# fib_backplate.net
KiCad netlist of a schematic drawn in EAGLE
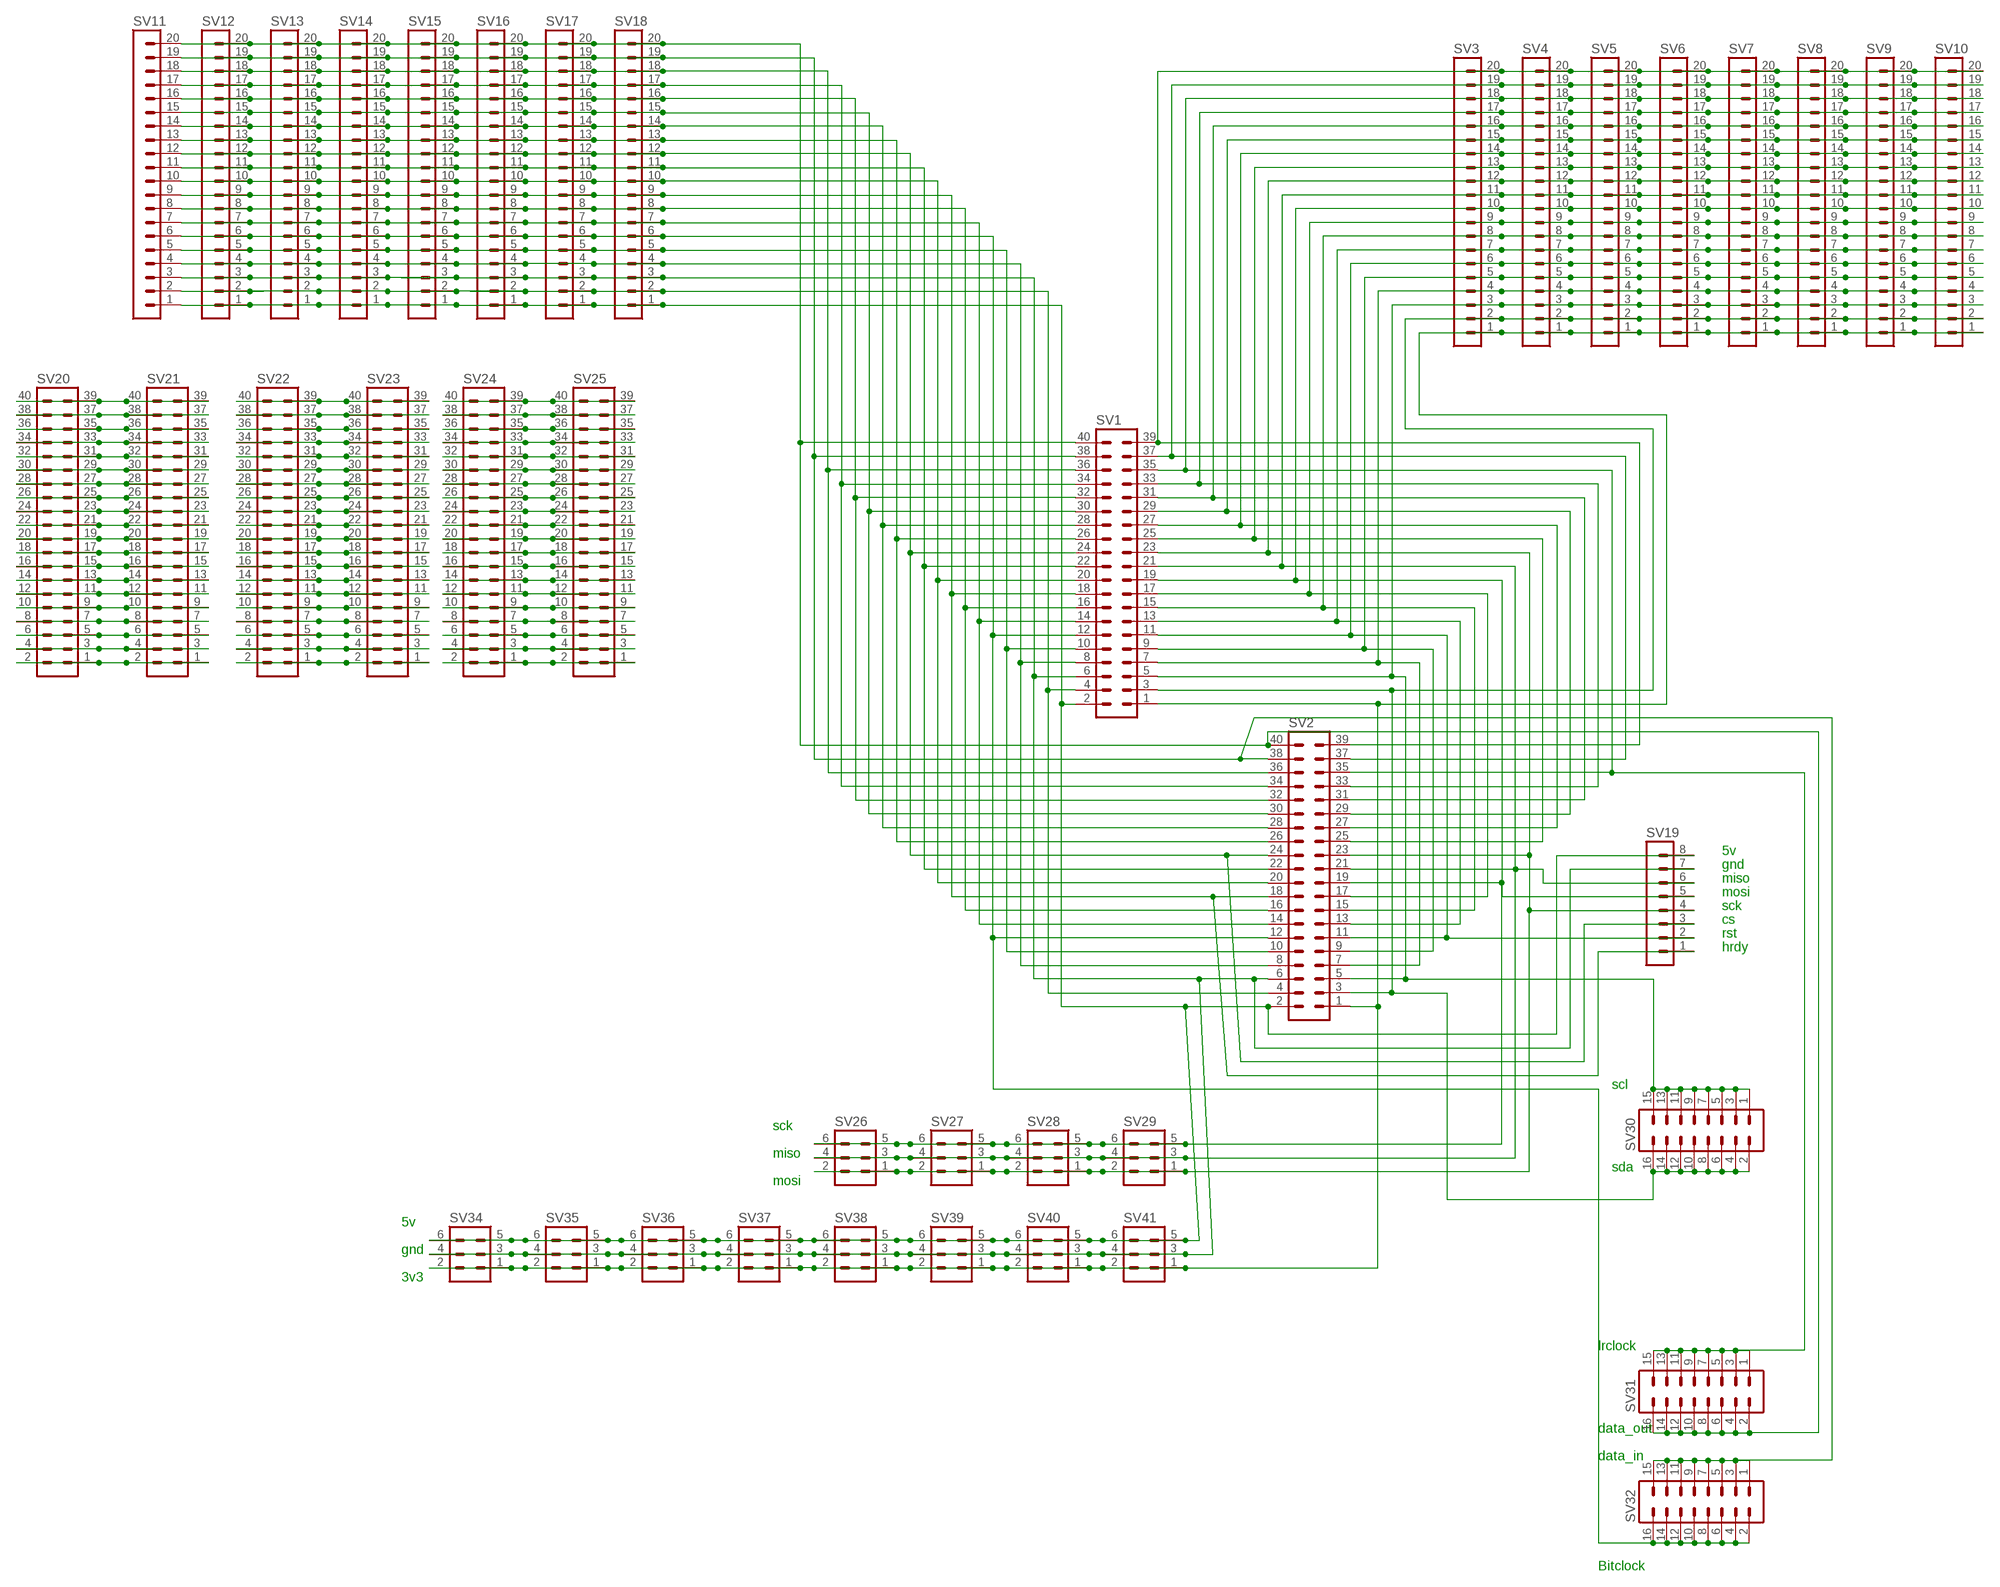
[diagram p0: schematic, sheet 1]

(export (version "E")
  (design (tool "Eeschema 10.0.6"))
  (components
    (comp (ref "SV1")
      (value "MA20-2")
      (footprint "eagle-import:MA20-2")
      (libsource (lib "eagle-import") (part "MA20-2"))
    )
    (comp (ref "SV2")
      (value "MA20-2")
      (footprint "eagle-import:MA20-2")
      (libsource (lib "eagle-import") (part "MA20-2"))
    )
    (comp (ref "SV3")
      (value "MA20-1L")
      (footprint "eagle-import:MA20-1L")
      (libsource (lib "eagle-import") (part "MA20-1L"))
    )
    (comp (ref "SV4")
      (value "MA20-1L")
      (footprint "eagle-import:MA20-1L")
      (libsource (lib "eagle-import") (part "MA20-1L"))
    )
    (comp (ref "SV5")
      (value "MA20-1L")
      (footprint "eagle-import:MA20-1L")
      (libsource (lib "eagle-import") (part "MA20-1L"))
    )
    (comp (ref "SV6")
      (value "MA20-1L")
      (footprint "eagle-import:MA20-1L")
      (libsource (lib "eagle-import") (part "MA20-1L"))
    )
    (comp (ref "SV7")
      (value "MA20-1L")
      (footprint "eagle-import:MA20-1L")
      (libsource (lib "eagle-import") (part "MA20-1L"))
    )
    (comp (ref "SV8")
      (value "MA20-1L")
      (footprint "eagle-import:MA20-1L")
      (libsource (lib "eagle-import") (part "MA20-1L"))
    )
    (comp (ref "SV9")
      (value "MA20-1L")
      (footprint "eagle-import:MA20-1L")
      (libsource (lib "eagle-import") (part "MA20-1L"))
    )
    (comp (ref "SV10")
      (value "MA20-1L")
      (footprint "eagle-import:MA20-1L")
      (libsource (lib "eagle-import") (part "MA20-1L"))
    )
    (comp (ref "SV11")
      (value "MA20-1L")
      (footprint "eagle-import:MA20-1L")
      (libsource (lib "eagle-import") (part "MA20-1L"))
    )
    (comp (ref "SV12")
      (value "MA20-1L")
      (footprint "eagle-import:MA20-1L")
      (libsource (lib "eagle-import") (part "MA20-1L"))
    )
    (comp (ref "SV13")
      (value "MA20-1L")
      (footprint "eagle-import:MA20-1L")
      (libsource (lib "eagle-import") (part "MA20-1L"))
    )
    (comp (ref "SV14")
      (value "MA20-1L")
      (footprint "eagle-import:MA20-1L")
      (libsource (lib "eagle-import") (part "MA20-1L"))
    )
    (comp (ref "SV15")
      (value "MA20-1L")
      (footprint "eagle-import:MA20-1L")
      (libsource (lib "eagle-import") (part "MA20-1L"))
    )
    (comp (ref "SV16")
      (value "MA20-1L")
      (footprint "eagle-import:MA20-1L")
      (libsource (lib "eagle-import") (part "MA20-1L"))
    )
    (comp (ref "SV17")
      (value "MA20-1L")
      (footprint "eagle-import:MA20-1L")
      (libsource (lib "eagle-import") (part "MA20-1L"))
    )
    (comp (ref "SV18")
      (value "MA20-1L")
      (footprint "eagle-import:MA20-1L")
      (libsource (lib "eagle-import") (part "MA20-1L"))
    )
    (comp (ref "SV19")
      (value "MA08-1")
      (footprint "eagle-import:MA08-1")
      (libsource (lib "eagle-import") (part "MA08-1"))
    )
    (comp (ref "SV20")
      (value "MA20-2")
      (footprint "eagle-import:MA20-2")
      (libsource (lib "eagle-import") (part "MA20-2"))
    )
    (comp (ref "SV21")
      (value "MA20-2")
      (footprint "eagle-import:MA20-2")
      (libsource (lib "eagle-import") (part "MA20-2"))
    )
    (comp (ref "SV22")
      (value "MA20-2")
      (footprint "eagle-import:MA20-2")
      (libsource (lib "eagle-import") (part "MA20-2"))
    )
    (comp (ref "SV23")
      (value "MA20-2")
      (footprint "eagle-import:MA20-2")
      (libsource (lib "eagle-import") (part "MA20-2"))
    )
    (comp (ref "SV24")
      (value "MA20-2")
      (footprint "eagle-import:MA20-2")
      (libsource (lib "eagle-import") (part "MA20-2"))
    )
    (comp (ref "SV25")
      (value "MA20-2")
      (footprint "eagle-import:MA20-2")
      (libsource (lib "eagle-import") (part "MA20-2"))
    )
    (comp (ref "SV26")
      (value "MA03-2")
      (footprint "eagle-import:MA03-2")
      (libsource (lib "eagle-import") (part "MA03-2"))
    )
    (comp (ref "SV27")
      (value "MA03-2")
      (footprint "eagle-import:MA03-2")
      (libsource (lib "eagle-import") (part "MA03-2"))
    )
    (comp (ref "SV28")
      (value "MA03-2")
      (footprint "eagle-import:MA03-2")
      (libsource (lib "eagle-import") (part "MA03-2"))
    )
    (comp (ref "SV29")
      (value "MA03-2")
      (footprint "eagle-import:MA03-2")
      (libsource (lib "eagle-import") (part "MA03-2"))
    )
    (comp (ref "SV30")
      (value "MA08-2")
      (footprint "eagle-import:MA08-2")
      (libsource (lib "eagle-import") (part "MA08-2"))
    )
    (comp (ref "SV31")
      (value "MA08-2")
      (footprint "eagle-import:MA08-2")
      (libsource (lib "eagle-import") (part "MA08-2"))
    )
    (comp (ref "SV32")
      (value "MA08-2")
      (footprint "eagle-import:MA08-2")
      (libsource (lib "eagle-import") (part "MA08-2"))
    )
    (comp (ref "SV34")
      (value "MA03-2")
      (footprint "eagle-import:MA03-2")
      (libsource (lib "eagle-import") (part "MA03-2"))
    )
    (comp (ref "SV35")
      (value "MA03-2")
      (footprint "eagle-import:MA03-2")
      (libsource (lib "eagle-import") (part "MA03-2"))
    )
    (comp (ref "SV36")
      (value "MA03-2")
      (footprint "eagle-import:MA03-2")
      (libsource (lib "eagle-import") (part "MA03-2"))
    )
    (comp (ref "SV37")
      (value "MA03-2")
      (footprint "eagle-import:MA03-2")
      (libsource (lib "eagle-import") (part "MA03-2"))
    )
    (comp (ref "SV38")
      (value "MA03-2")
      (footprint "eagle-import:MA03-2")
      (libsource (lib "eagle-import") (part "MA03-2"))
    )
    (comp (ref "SV39")
      (value "MA03-2")
      (footprint "eagle-import:MA03-2")
      (libsource (lib "eagle-import") (part "MA03-2"))
    )
    (comp (ref "SV40")
      (value "MA03-2")
      (footprint "eagle-import:MA03-2")
      (libsource (lib "eagle-import") (part "MA03-2"))
    )
    (comp (ref "SV41")
      (value "MA03-2")
      (footprint "eagle-import:MA03-2")
      (libsource (lib "eagle-import") (part "MA03-2"))
    )
  )
  (nets
    (net (code "1") (name "Net-(SV1-Pad1)") (class "Default")
      (node (ref "SV1") (pin "1") (pinfunction "1_1") (pintype "passive"))
      (node (ref "SV10") (pin "1") (pinfunction "1_1") (pintype "passive"))
      (node (ref "SV2") (pin "1") (pinfunction "1_1") (pintype "passive"))
      (node (ref "SV3") (pin "1") (pinfunction "1_1") (pintype "passive"))
      (node (ref "SV34") (pin "1") (pinfunction "1_1") (pintype "passive"))
      (node (ref "SV34") (pin "2") (pinfunction "2_2") (pintype "passive"))
      (node (ref "SV35") (pin "1") (pinfunction "1_1") (pintype "passive"))
      (node (ref "SV35") (pin "2") (pinfunction "2_2") (pintype "passive"))
      (node (ref "SV36") (pin "1") (pinfunction "1_1") (pintype "passive"))
      (node (ref "SV36") (pin "2") (pinfunction "2_2") (pintype "passive"))
      (node (ref "SV37") (pin "1") (pinfunction "1_1") (pintype "passive"))
      (node (ref "SV37") (pin "2") (pinfunction "2_2") (pintype "passive"))
      (node (ref "SV38") (pin "1") (pinfunction "1_1") (pintype "passive"))
      (node (ref "SV38") (pin "2") (pinfunction "2_2") (pintype "passive"))
      (node (ref "SV39") (pin "1") (pinfunction "1_1") (pintype "passive"))
      (node (ref "SV39") (pin "2") (pinfunction "2_2") (pintype "passive"))
      (node (ref "SV4") (pin "1") (pinfunction "1_1") (pintype "passive"))
      (node (ref "SV40") (pin "1") (pinfunction "1_1") (pintype "passive"))
      (node (ref "SV40") (pin "2") (pinfunction "2_2") (pintype "passive"))
      (node (ref "SV41") (pin "1") (pinfunction "1_1") (pintype "passive"))
      (node (ref "SV41") (pin "2") (pinfunction "2_2") (pintype "passive"))
      (node (ref "SV5") (pin "1") (pinfunction "1_1") (pintype "passive"))
      (node (ref "SV6") (pin "1") (pinfunction "1_1") (pintype "passive"))
      (node (ref "SV7") (pin "1") (pinfunction "1_1") (pintype "passive"))
      (node (ref "SV8") (pin "1") (pinfunction "1_1") (pintype "passive"))
      (node (ref "SV9") (pin "1") (pinfunction "1_1") (pintype "passive"))
    )
    (net (code "2") (name "Net-(SV1-Pad2)") (class "Default")
      (node (ref "SV1") (pin "2") (pinfunction "2_2") (pintype "passive"))
      (node (ref "SV11") (pin "1") (pinfunction "1_1") (pintype "passive"))
      (node (ref "SV12") (pin "1") (pinfunction "1_1") (pintype "passive"))
      (node (ref "SV13") (pin "1") (pinfunction "1_1") (pintype "passive"))
      (node (ref "SV14") (pin "1") (pinfunction "1_1") (pintype "passive"))
      (node (ref "SV15") (pin "1") (pinfunction "1_1") (pintype "passive"))
      (node (ref "SV16") (pin "1") (pinfunction "1_1") (pintype "passive"))
      (node (ref "SV17") (pin "1") (pinfunction "1_1") (pintype "passive"))
      (node (ref "SV18") (pin "1") (pinfunction "1_1") (pintype "passive"))
      (node (ref "SV19") (pin "8") (pinfunction "8_8") (pintype "passive"))
      (node (ref "SV2") (pin "2") (pinfunction "2_2") (pintype "passive"))
      (node (ref "SV34") (pin "5") (pinfunction "5_5") (pintype "passive"))
      (node (ref "SV34") (pin "6") (pinfunction "6_6") (pintype "passive"))
      (node (ref "SV35") (pin "5") (pinfunction "5_5") (pintype "passive"))
      (node (ref "SV35") (pin "6") (pinfunction "6_6") (pintype "passive"))
      (node (ref "SV36") (pin "5") (pinfunction "5_5") (pintype "passive"))
      (node (ref "SV36") (pin "6") (pinfunction "6_6") (pintype "passive"))
      (node (ref "SV37") (pin "5") (pinfunction "5_5") (pintype "passive"))
      (node (ref "SV37") (pin "6") (pinfunction "6_6") (pintype "passive"))
      (node (ref "SV38") (pin "5") (pinfunction "5_5") (pintype "passive"))
      (node (ref "SV38") (pin "6") (pinfunction "6_6") (pintype "passive"))
      (node (ref "SV39") (pin "5") (pinfunction "5_5") (pintype "passive"))
      (node (ref "SV39") (pin "6") (pinfunction "6_6") (pintype "passive"))
      (node (ref "SV40") (pin "5") (pinfunction "5_5") (pintype "passive"))
      (node (ref "SV40") (pin "6") (pinfunction "6_6") (pintype "passive"))
      (node (ref "SV41") (pin "5") (pinfunction "5_5") (pintype "passive"))
      (node (ref "SV41") (pin "6") (pinfunction "6_6") (pintype "passive"))
    )
    (net (code "3") (name "Net-(SV1-Pad3)") (class "Default")
      (node (ref "SV1") (pin "3") (pinfunction "3_3") (pintype "passive"))
      (node (ref "SV10") (pin "2") (pinfunction "2_2") (pintype "passive"))
      (node (ref "SV2") (pin "3") (pinfunction "3_3") (pintype "passive"))
      (node (ref "SV3") (pin "2") (pinfunction "2_2") (pintype "passive"))
      (node (ref "SV30") (pin "10") (pinfunction "10_10") (pintype "passive"))
      (node (ref "SV30") (pin "12") (pinfunction "12_12") (pintype "passive"))
      (node (ref "SV30") (pin "14") (pinfunction "14_14") (pintype "passive"))
      (node (ref "SV30") (pin "16") (pinfunction "16_16") (pintype "passive"))
      (node (ref "SV30") (pin "2") (pinfunction "2_2") (pintype "passive"))
      (node (ref "SV30") (pin "4") (pinfunction "4_4") (pintype "passive"))
      (node (ref "SV30") (pin "6") (pinfunction "6_6") (pintype "passive"))
      (node (ref "SV30") (pin "8") (pinfunction "8_8") (pintype "passive"))
      (node (ref "SV4") (pin "2") (pinfunction "2_2") (pintype "passive"))
      (node (ref "SV5") (pin "2") (pinfunction "2_2") (pintype "passive"))
      (node (ref "SV6") (pin "2") (pinfunction "2_2") (pintype "passive"))
      (node (ref "SV7") (pin "2") (pinfunction "2_2") (pintype "passive"))
      (node (ref "SV8") (pin "2") (pinfunction "2_2") (pintype "passive"))
      (node (ref "SV9") (pin "2") (pinfunction "2_2") (pintype "passive"))
    )
    (net (code "4") (name "Net-(SV1-Pad4)") (class "Default")
      (node (ref "SV1") (pin "4") (pinfunction "4_4") (pintype "passive"))
      (node (ref "SV11") (pin "2") (pinfunction "2_2") (pintype "passive"))
      (node (ref "SV12") (pin "2") (pinfunction "2_2") (pintype "passive"))
      (node (ref "SV13") (pin "2") (pinfunction "2_2") (pintype "passive"))
      (node (ref "SV14") (pin "2") (pinfunction "2_2") (pintype "passive"))
      (node (ref "SV15") (pin "2") (pinfunction "2_2") (pintype "passive"))
      (node (ref "SV16") (pin "2") (pinfunction "2_2") (pintype "passive"))
      (node (ref "SV17") (pin "2") (pinfunction "2_2") (pintype "passive"))
      (node (ref "SV18") (pin "2") (pinfunction "2_2") (pintype "passive"))
      (node (ref "SV2") (pin "4") (pinfunction "4_4") (pintype "passive"))
    )
    (net (code "5") (name "Net-(SV1-Pad5)") (class "Default")
      (node (ref "SV1") (pin "5") (pinfunction "5_5") (pintype "passive"))
      (node (ref "SV10") (pin "3") (pinfunction "3_3") (pintype "passive"))
      (node (ref "SV2") (pin "5") (pinfunction "5_5") (pintype "passive"))
      (node (ref "SV3") (pin "3") (pinfunction "3_3") (pintype "passive"))
      (node (ref "SV30") (pin "1") (pinfunction "1_1") (pintype "passive"))
      (node (ref "SV30") (pin "11") (pinfunction "11_11") (pintype "passive"))
      (node (ref "SV30") (pin "13") (pinfunction "13_13") (pintype "passive"))
      (node (ref "SV30") (pin "15") (pinfunction "15_15") (pintype "passive"))
      (node (ref "SV30") (pin "3") (pinfunction "3_3") (pintype "passive"))
      (node (ref "SV30") (pin "5") (pinfunction "5_5") (pintype "passive"))
      (node (ref "SV30") (pin "7") (pinfunction "7_7") (pintype "passive"))
      (node (ref "SV30") (pin "9") (pinfunction "9_9") (pintype "passive"))
      (node (ref "SV4") (pin "3") (pinfunction "3_3") (pintype "passive"))
      (node (ref "SV5") (pin "3") (pinfunction "3_3") (pintype "passive"))
      (node (ref "SV6") (pin "3") (pinfunction "3_3") (pintype "passive"))
      (node (ref "SV7") (pin "3") (pinfunction "3_3") (pintype "passive"))
      (node (ref "SV8") (pin "3") (pinfunction "3_3") (pintype "passive"))
      (node (ref "SV9") (pin "3") (pinfunction "3_3") (pintype "passive"))
    )
    (net (code "6") (name "Net-(SV1-Pad6)") (class "Default")
      (node (ref "SV1") (pin "6") (pinfunction "6_6") (pintype "passive"))
      (node (ref "SV11") (pin "3") (pinfunction "3_3") (pintype "passive"))
      (node (ref "SV12") (pin "3") (pinfunction "3_3") (pintype "passive"))
      (node (ref "SV13") (pin "3") (pinfunction "3_3") (pintype "passive"))
      (node (ref "SV14") (pin "3") (pinfunction "3_3") (pintype "passive"))
      (node (ref "SV15") (pin "3") (pinfunction "3_3") (pintype "passive"))
      (node (ref "SV16") (pin "3") (pinfunction "3_3") (pintype "passive"))
      (node (ref "SV17") (pin "3") (pinfunction "3_3") (pintype "passive"))
      (node (ref "SV18") (pin "3") (pinfunction "3_3") (pintype "passive"))
      (node (ref "SV19") (pin "7") (pinfunction "7_7") (pintype "passive"))
      (node (ref "SV2") (pin "6") (pinfunction "6_6") (pintype "passive"))
      (node (ref "SV34") (pin "3") (pinfunction "3_3") (pintype "passive"))
      (node (ref "SV34") (pin "4") (pinfunction "4_4") (pintype "passive"))
      (node (ref "SV35") (pin "3") (pinfunction "3_3") (pintype "passive"))
      (node (ref "SV35") (pin "4") (pinfunction "4_4") (pintype "passive"))
      (node (ref "SV36") (pin "3") (pinfunction "3_3") (pintype "passive"))
      (node (ref "SV36") (pin "4") (pinfunction "4_4") (pintype "passive"))
      (node (ref "SV37") (pin "3") (pinfunction "3_3") (pintype "passive"))
      (node (ref "SV37") (pin "4") (pinfunction "4_4") (pintype "passive"))
      (node (ref "SV38") (pin "3") (pinfunction "3_3") (pintype "passive"))
      (node (ref "SV38") (pin "4") (pinfunction "4_4") (pintype "passive"))
      (node (ref "SV39") (pin "3") (pinfunction "3_3") (pintype "passive"))
      (node (ref "SV39") (pin "4") (pinfunction "4_4") (pintype "passive"))
      (node (ref "SV40") (pin "3") (pinfunction "3_3") (pintype "passive"))
      (node (ref "SV40") (pin "4") (pinfunction "4_4") (pintype "passive"))
      (node (ref "SV41") (pin "3") (pinfunction "3_3") (pintype "passive"))
      (node (ref "SV41") (pin "4") (pinfunction "4_4") (pintype "passive"))
    )
    (net (code "7") (name "Net-(SV1-Pad7)") (class "Default")
      (node (ref "SV1") (pin "7") (pinfunction "7_7") (pintype "passive"))
      (node (ref "SV10") (pin "4") (pinfunction "4_4") (pintype "passive"))
      (node (ref "SV2") (pin "7") (pinfunction "7_7") (pintype "passive"))
      (node (ref "SV3") (pin "4") (pinfunction "4_4") (pintype "passive"))
      (node (ref "SV4") (pin "4") (pinfunction "4_4") (pintype "passive"))
      (node (ref "SV5") (pin "4") (pinfunction "4_4") (pintype "passive"))
      (node (ref "SV6") (pin "4") (pinfunction "4_4") (pintype "passive"))
      (node (ref "SV7") (pin "4") (pinfunction "4_4") (pintype "passive"))
      (node (ref "SV8") (pin "4") (pinfunction "4_4") (pintype "passive"))
      (node (ref "SV9") (pin "4") (pinfunction "4_4") (pintype "passive"))
    )
    (net (code "8") (name "Net-(SV1-Pad8)") (class "Default")
      (node (ref "SV1") (pin "8") (pinfunction "8_8") (pintype "passive"))
      (node (ref "SV11") (pin "4") (pinfunction "4_4") (pintype "passive"))
      (node (ref "SV12") (pin "4") (pinfunction "4_4") (pintype "passive"))
      (node (ref "SV13") (pin "4") (pinfunction "4_4") (pintype "passive"))
      (node (ref "SV14") (pin "4") (pinfunction "4_4") (pintype "passive"))
      (node (ref "SV15") (pin "4") (pinfunction "4_4") (pintype "passive"))
      (node (ref "SV16") (pin "4") (pinfunction "4_4") (pintype "passive"))
      (node (ref "SV17") (pin "4") (pinfunction "4_4") (pintype "passive"))
      (node (ref "SV18") (pin "4") (pinfunction "4_4") (pintype "passive"))
      (node (ref "SV2") (pin "8") (pinfunction "8_8") (pintype "passive"))
    )
    (net (code "9") (name "Net-(SV1-Pad9)") (class "Default")
      (node (ref "SV1") (pin "9") (pinfunction "9_9") (pintype "passive"))
      (node (ref "SV10") (pin "5") (pinfunction "5_5") (pintype "passive"))
      (node (ref "SV2") (pin "9") (pinfunction "9_9") (pintype "passive"))
      (node (ref "SV3") (pin "5") (pinfunction "5_5") (pintype "passive"))
      (node (ref "SV4") (pin "5") (pinfunction "5_5") (pintype "passive"))
      (node (ref "SV5") (pin "5") (pinfunction "5_5") (pintype "passive"))
      (node (ref "SV6") (pin "5") (pinfunction "5_5") (pintype "passive"))
      (node (ref "SV7") (pin "5") (pinfunction "5_5") (pintype "passive"))
      (node (ref "SV8") (pin "5") (pinfunction "5_5") (pintype "passive"))
      (node (ref "SV9") (pin "5") (pinfunction "5_5") (pintype "passive"))
    )
    (net (code "10") (name "Net-(SV1-Pad10)") (class "Default")
      (node (ref "SV1") (pin "10") (pinfunction "10_10") (pintype "passive"))
      (node (ref "SV11") (pin "5") (pinfunction "5_5") (pintype "passive"))
      (node (ref "SV12") (pin "5") (pinfunction "5_5") (pintype "passive"))
      (node (ref "SV13") (pin "5") (pinfunction "5_5") (pintype "passive"))
      (node (ref "SV14") (pin "5") (pinfunction "5_5") (pintype "passive"))
      (node (ref "SV15") (pin "5") (pinfunction "5_5") (pintype "passive"))
      (node (ref "SV16") (pin "5") (pinfunction "5_5") (pintype "passive"))
      (node (ref "SV17") (pin "5") (pinfunction "5_5") (pintype "passive"))
      (node (ref "SV18") (pin "5") (pinfunction "5_5") (pintype "passive"))
      (node (ref "SV2") (pin "10") (pinfunction "10_10") (pintype "passive"))
    )
    (net (code "11") (name "Net-(SV1-Pad11)") (class "Default")
      (node (ref "SV1") (pin "11") (pinfunction "11_11") (pintype "passive"))
      (node (ref "SV10") (pin "6") (pinfunction "6_6") (pintype "passive"))
      (node (ref "SV19") (pin "2") (pinfunction "2_2") (pintype "passive"))
      (node (ref "SV2") (pin "11") (pinfunction "11_11") (pintype "passive"))
      (node (ref "SV3") (pin "6") (pinfunction "6_6") (pintype "passive"))
      (node (ref "SV4") (pin "6") (pinfunction "6_6") (pintype "passive"))
      (node (ref "SV5") (pin "6") (pinfunction "6_6") (pintype "passive"))
      (node (ref "SV6") (pin "6") (pinfunction "6_6") (pintype "passive"))
      (node (ref "SV7") (pin "6") (pinfunction "6_6") (pintype "passive"))
      (node (ref "SV8") (pin "6") (pinfunction "6_6") (pintype "passive"))
      (node (ref "SV9") (pin "6") (pinfunction "6_6") (pintype "passive"))
    )
    (net (code "12") (name "Net-(SV1-Pad12)") (class "Default")
      (node (ref "SV1") (pin "12") (pinfunction "12_12") (pintype "passive"))
      (node (ref "SV11") (pin "6") (pinfunction "6_6") (pintype "passive"))
      (node (ref "SV12") (pin "6") (pinfunction "6_6") (pintype "passive"))
      (node (ref "SV13") (pin "6") (pinfunction "6_6") (pintype "passive"))
      (node (ref "SV14") (pin "6") (pinfunction "6_6") (pintype "passive"))
      (node (ref "SV15") (pin "6") (pinfunction "6_6") (pintype "passive"))
      (node (ref "SV16") (pin "6") (pinfunction "6_6") (pintype "passive"))
      (node (ref "SV17") (pin "6") (pinfunction "6_6") (pintype "passive"))
      (node (ref "SV18") (pin "6") (pinfunction "6_6") (pintype "passive"))
      (node (ref "SV2") (pin "12") (pinfunction "12_12") (pintype "passive"))
      (node (ref "SV32") (pin "10") (pinfunction "10_10") (pintype "passive"))
      (node (ref "SV32") (pin "12") (pinfunction "12_12") (pintype "passive"))
      (node (ref "SV32") (pin "14") (pinfunction "14_14") (pintype "passive"))
      (node (ref "SV32") (pin "16") (pinfunction "16_16") (pintype "passive"))
      (node (ref "SV32") (pin "2") (pinfunction "2_2") (pintype "passive"))
      (node (ref "SV32") (pin "4") (pinfunction "4_4") (pintype "passive"))
      (node (ref "SV32") (pin "6") (pinfunction "6_6") (pintype "passive"))
      (node (ref "SV32") (pin "8") (pinfunction "8_8") (pintype "passive"))
    )
    (net (code "13") (name "Net-(SV1-Pad13)") (class "Default")
      (node (ref "SV1") (pin "13") (pinfunction "13_13") (pintype "passive"))
      (node (ref "SV10") (pin "7") (pinfunction "7_7") (pintype "passive"))
      (node (ref "SV2") (pin "13") (pinfunction "13_13") (pintype "passive"))
      (node (ref "SV3") (pin "7") (pinfunction "7_7") (pintype "passive"))
      (node (ref "SV4") (pin "7") (pinfunction "7_7") (pintype "passive"))
      (node (ref "SV5") (pin "7") (pinfunction "7_7") (pintype "passive"))
      (node (ref "SV6") (pin "7") (pinfunction "7_7") (pintype "passive"))
      (node (ref "SV7") (pin "7") (pinfunction "7_7") (pintype "passive"))
      (node (ref "SV8") (pin "7") (pinfunction "7_7") (pintype "passive"))
      (node (ref "SV9") (pin "7") (pinfunction "7_7") (pintype "passive"))
    )
    (net (code "14") (name "Net-(SV1-Pad14)") (class "Default")
      (node (ref "SV1") (pin "14") (pinfunction "14_14") (pintype "passive"))
      (node (ref "SV11") (pin "7") (pinfunction "7_7") (pintype "passive"))
      (node (ref "SV12") (pin "7") (pinfunction "7_7") (pintype "passive"))
      (node (ref "SV13") (pin "7") (pinfunction "7_7") (pintype "passive"))
      (node (ref "SV14") (pin "7") (pinfunction "7_7") (pintype "passive"))
      (node (ref "SV15") (pin "7") (pinfunction "7_7") (pintype "passive"))
      (node (ref "SV16") (pin "7") (pinfunction "7_7") (pintype "passive"))
      (node (ref "SV17") (pin "7") (pinfunction "7_7") (pintype "passive"))
      (node (ref "SV18") (pin "7") (pinfunction "7_7") (pintype "passive"))
      (node (ref "SV2") (pin "14") (pinfunction "14_14") (pintype "passive"))
    )
    (net (code "15") (name "Net-(SV1-Pad15)") (class "Default")
      (node (ref "SV1") (pin "15") (pinfunction "15_15") (pintype "passive"))
      (node (ref "SV10") (pin "8") (pinfunction "8_8") (pintype "passive"))
      (node (ref "SV2") (pin "15") (pinfunction "15_15") (pintype "passive"))
      (node (ref "SV3") (pin "8") (pinfunction "8_8") (pintype "passive"))
      (node (ref "SV4") (pin "8") (pinfunction "8_8") (pintype "passive"))
      (node (ref "SV5") (pin "8") (pinfunction "8_8") (pintype "passive"))
      (node (ref "SV6") (pin "8") (pinfunction "8_8") (pintype "passive"))
      (node (ref "SV7") (pin "8") (pinfunction "8_8") (pintype "passive"))
      (node (ref "SV8") (pin "8") (pinfunction "8_8") (pintype "passive"))
      (node (ref "SV9") (pin "8") (pinfunction "8_8") (pintype "passive"))
    )
    (net (code "16") (name "Net-(SV1-Pad16)") (class "Default")
      (node (ref "SV1") (pin "16") (pinfunction "16_16") (pintype "passive"))
      (node (ref "SV11") (pin "8") (pinfunction "8_8") (pintype "passive"))
      (node (ref "SV12") (pin "8") (pinfunction "8_8") (pintype "passive"))
      (node (ref "SV13") (pin "8") (pinfunction "8_8") (pintype "passive"))
      (node (ref "SV14") (pin "8") (pinfunction "8_8") (pintype "passive"))
      (node (ref "SV15") (pin "8") (pinfunction "8_8") (pintype "passive"))
      (node (ref "SV16") (pin "8") (pinfunction "8_8") (pintype "passive"))
      (node (ref "SV17") (pin "8") (pinfunction "8_8") (pintype "passive"))
      (node (ref "SV18") (pin "8") (pinfunction "8_8") (pintype "passive"))
      (node (ref "SV2") (pin "16") (pinfunction "16_16") (pintype "passive"))
    )
    (net (code "17") (name "Net-(SV1-Pad17)") (class "Default")
      (node (ref "SV1") (pin "17") (pinfunction "17_17") (pintype "passive"))
      (node (ref "SV10") (pin "9") (pinfunction "9_9") (pintype "passive"))
      (node (ref "SV2") (pin "17") (pinfunction "17_17") (pintype "passive"))
      (node (ref "SV3") (pin "9") (pinfunction "9_9") (pintype "passive"))
      (node (ref "SV4") (pin "9") (pinfunction "9_9") (pintype "passive"))
      (node (ref "SV5") (pin "9") (pinfunction "9_9") (pintype "passive"))
      (node (ref "SV6") (pin "9") (pinfunction "9_9") (pintype "passive"))
      (node (ref "SV7") (pin "9") (pinfunction "9_9") (pintype "passive"))
      (node (ref "SV8") (pin "9") (pinfunction "9_9") (pintype "passive"))
      (node (ref "SV9") (pin "9") (pinfunction "9_9") (pintype "passive"))
    )
    (net (code "18") (name "Net-(SV1-Pad18)") (class "Default")
      (node (ref "SV1") (pin "18") (pinfunction "18_18") (pintype "passive"))
      (node (ref "SV11") (pin "9") (pinfunction "9_9") (pintype "passive"))
      (node (ref "SV12") (pin "9") (pinfunction "9_9") (pintype "passive"))
      (node (ref "SV13") (pin "9") (pinfunction "9_9") (pintype "passive"))
      (node (ref "SV14") (pin "9") (pinfunction "9_9") (pintype "passive"))
      (node (ref "SV15") (pin "9") (pinfunction "9_9") (pintype "passive"))
      (node (ref "SV16") (pin "9") (pinfunction "9_9") (pintype "passive"))
      (node (ref "SV17") (pin "9") (pinfunction "9_9") (pintype "passive"))
      (node (ref "SV18") (pin "9") (pinfunction "9_9") (pintype "passive"))
      (node (ref "SV19") (pin "1") (pinfunction "1_1") (pintype "passive"))
      (node (ref "SV2") (pin "18") (pinfunction "18_18") (pintype "passive"))
    )
    (net (code "19") (name "Net-(SV1-Pad19)") (class "Default")
      (node (ref "SV1") (pin "19") (pinfunction "19_19") (pintype "passive"))
      (node (ref "SV10") (pin "10") (pinfunction "10_10") (pintype "passive"))
      (node (ref "SV19") (pin "5") (pinfunction "5_5") (pintype "passive"))
      (node (ref "SV2") (pin "19") (pinfunction "19_19") (pintype "passive"))
      (node (ref "SV26") (pin "5") (pinfunction "5_5") (pintype "passive"))
      (node (ref "SV26") (pin "6") (pinfunction "6_6") (pintype "passive"))
      (node (ref "SV27") (pin "5") (pinfunction "5_5") (pintype "passive"))
      (node (ref "SV27") (pin "6") (pinfunction "6_6") (pintype "passive"))
      (node (ref "SV28") (pin "5") (pinfunction "5_5") (pintype "passive"))
      (node (ref "SV28") (pin "6") (pinfunction "6_6") (pintype "passive"))
      (node (ref "SV29") (pin "5") (pinfunction "5_5") (pintype "passive"))
      (node (ref "SV29") (pin "6") (pinfunction "6_6") (pintype "passive"))
      (node (ref "SV3") (pin "10") (pinfunction "10_10") (pintype "passive"))
      (node (ref "SV4") (pin "10") (pinfunction "10_10") (pintype "passive"))
      (node (ref "SV5") (pin "10") (pinfunction "10_10") (pintype "passive"))
      (node (ref "SV6") (pin "10") (pinfunction "10_10") (pintype "passive"))
      (node (ref "SV7") (pin "10") (pinfunction "10_10") (pintype "passive"))
      (node (ref "SV8") (pin "10") (pinfunction "10_10") (pintype "passive"))
      (node (ref "SV9") (pin "10") (pinfunction "10_10") (pintype "passive"))
    )
    (net (code "20") (name "Net-(SV1-Pad20)") (class "Default")
      (node (ref "SV1") (pin "20") (pinfunction "20_20") (pintype "passive"))
      (node (ref "SV11") (pin "10") (pinfunction "10_10") (pintype "passive"))
      (node (ref "SV12") (pin "10") (pinfunction "10_10") (pintype "passive"))
      (node (ref "SV13") (pin "10") (pinfunction "10_10") (pintype "passive"))
      (node (ref "SV14") (pin "10") (pinfunction "10_10") (pintype "passive"))
      (node (ref "SV15") (pin "10") (pinfunction "10_10") (pintype "passive"))
      (node (ref "SV16") (pin "10") (pinfunction "10_10") (pintype "passive"))
      (node (ref "SV17") (pin "10") (pinfunction "10_10") (pintype "passive"))
      (node (ref "SV18") (pin "10") (pinfunction "10_10") (pintype "passive"))
      (node (ref "SV2") (pin "20") (pinfunction "20_20") (pintype "passive"))
    )
    (net (code "21") (name "Net-(SV1-Pad21)") (class "Default")
      (node (ref "SV1") (pin "21") (pinfunction "21_21") (pintype "passive"))
      (node (ref "SV10") (pin "11") (pinfunction "11_11") (pintype "passive"))
      (node (ref "SV19") (pin "6") (pinfunction "6_6") (pintype "passive"))
      (node (ref "SV2") (pin "21") (pinfunction "21_21") (pintype "passive"))
      (node (ref "SV26") (pin "3") (pinfunction "3_3") (pintype "passive"))
      (node (ref "SV26") (pin "4") (pinfunction "4_4") (pintype "passive"))
      (node (ref "SV27") (pin "3") (pinfunction "3_3") (pintype "passive"))
      (node (ref "SV27") (pin "4") (pinfunction "4_4") (pintype "passive"))
      (node (ref "SV28") (pin "3") (pinfunction "3_3") (pintype "passive"))
      (node (ref "SV28") (pin "4") (pinfunction "4_4") (pintype "passive"))
      (node (ref "SV29") (pin "3") (pinfunction "3_3") (pintype "passive"))
      (node (ref "SV29") (pin "4") (pinfunction "4_4") (pintype "passive"))
      (node (ref "SV3") (pin "11") (pinfunction "11_11") (pintype "passive"))
      (node (ref "SV4") (pin "11") (pinfunction "11_11") (pintype "passive"))
      (node (ref "SV5") (pin "11") (pinfunction "11_11") (pintype "passive"))
      (node (ref "SV6") (pin "11") (pinfunction "11_11") (pintype "passive"))
      (node (ref "SV7") (pin "11") (pinfunction "11_11") (pintype "passive"))
      (node (ref "SV8") (pin "11") (pinfunction "11_11") (pintype "passive"))
      (node (ref "SV9") (pin "11") (pinfunction "11_11") (pintype "passive"))
    )
    (net (code "22") (name "Net-(SV1-Pad22)") (class "Default")
      (node (ref "SV1") (pin "22") (pinfunction "22_22") (pintype "passive"))
      (node (ref "SV11") (pin "11") (pinfunction "11_11") (pintype "passive"))
      (node (ref "SV12") (pin "11") (pinfunction "11_11") (pintype "passive"))
      (node (ref "SV13") (pin "11") (pinfunction "11_11") (pintype "passive"))
      (node (ref "SV14") (pin "11") (pinfunction "11_11") (pintype "passive"))
      (node (ref "SV15") (pin "11") (pinfunction "11_11") (pintype "passive"))
      (node (ref "SV16") (pin "11") (pinfunction "11_11") (pintype "passive"))
      (node (ref "SV17") (pin "11") (pinfunction "11_11") (pintype "passive"))
      (node (ref "SV18") (pin "11") (pinfunction "11_11") (pintype "passive"))
      (node (ref "SV2") (pin "22") (pinfunction "22_22") (pintype "passive"))
    )
    (net (code "23") (name "Net-(SV1-Pad23)") (class "Default")
      (node (ref "SV1") (pin "23") (pinfunction "23_23") (pintype "passive"))
      (node (ref "SV10") (pin "12") (pinfunction "12_12") (pintype "passive"))
      (node (ref "SV19") (pin "4") (pinfunction "4_4") (pintype "passive"))
      (node (ref "SV2") (pin "23") (pinfunction "23_23") (pintype "passive"))
      (node (ref "SV26") (pin "1") (pinfunction "1_1") (pintype "passive"))
      (node (ref "SV26") (pin "2") (pinfunction "2_2") (pintype "passive"))
      (node (ref "SV27") (pin "1") (pinfunction "1_1") (pintype "passive"))
      (node (ref "SV27") (pin "2") (pinfunction "2_2") (pintype "passive"))
      (node (ref "SV28") (pin "1") (pinfunction "1_1") (pintype "passive"))
      (node (ref "SV28") (pin "2") (pinfunction "2_2") (pintype "passive"))
      (node (ref "SV29") (pin "1") (pinfunction "1_1") (pintype "passive"))
      (node (ref "SV29") (pin "2") (pinfunction "2_2") (pintype "passive"))
      (node (ref "SV3") (pin "12") (pinfunction "12_12") (pintype "passive"))
      (node (ref "SV4") (pin "12") (pinfunction "12_12") (pintype "passive"))
      (node (ref "SV5") (pin "12") (pinfunction "12_12") (pintype "passive"))
      (node (ref "SV6") (pin "12") (pinfunction "12_12") (pintype "passive"))
      (node (ref "SV7") (pin "12") (pinfunction "12_12") (pintype "passive"))
      (node (ref "SV8") (pin "12") (pinfunction "12_12") (pintype "passive"))
      (node (ref "SV9") (pin "12") (pinfunction "12_12") (pintype "passive"))
    )
    (net (code "24") (name "Net-(SV1-Pad24)") (class "Default")
      (node (ref "SV1") (pin "24") (pinfunction "24_24") (pintype "passive"))
      (node (ref "SV11") (pin "12") (pinfunction "12_12") (pintype "passive"))
      (node (ref "SV12") (pin "12") (pinfunction "12_12") (pintype "passive"))
      (node (ref "SV13") (pin "12") (pinfunction "12_12") (pintype "passive"))
      (node (ref "SV14") (pin "12") (pinfunction "12_12") (pintype "passive"))
      (node (ref "SV15") (pin "12") (pinfunction "12_12") (pintype "passive"))
      (node (ref "SV16") (pin "12") (pinfunction "12_12") (pintype "passive"))
      (node (ref "SV17") (pin "12") (pinfunction "12_12") (pintype "passive"))
      (node (ref "SV18") (pin "12") (pinfunction "12_12") (pintype "passive"))
      (node (ref "SV19") (pin "3") (pinfunction "3_3") (pintype "passive"))
      (node (ref "SV2") (pin "24") (pinfunction "24_24") (pintype "passive"))
    )
    (net (code "25") (name "Net-(SV1-Pad25)") (class "Default")
      (node (ref "SV1") (pin "25") (pinfunction "25_25") (pintype "passive"))
      (node (ref "SV10") (pin "13") (pinfunction "13_13") (pintype "passive"))
      (node (ref "SV2") (pin "25") (pinfunction "25_25") (pintype "passive"))
      (node (ref "SV3") (pin "13") (pinfunction "13_13") (pintype "passive"))
      (node (ref "SV4") (pin "13") (pinfunction "13_13") (pintype "passive"))
      (node (ref "SV5") (pin "13") (pinfunction "13_13") (pintype "passive"))
      (node (ref "SV6") (pin "13") (pinfunction "13_13") (pintype "passive"))
      (node (ref "SV7") (pin "13") (pinfunction "13_13") (pintype "passive"))
      (node (ref "SV8") (pin "13") (pinfunction "13_13") (pintype "passive"))
      (node (ref "SV9") (pin "13") (pinfunction "13_13") (pintype "passive"))
    )
    (net (code "26") (name "Net-(SV1-Pad26)") (class "Default")
      (node (ref "SV1") (pin "26") (pinfunction "26_26") (pintype "passive"))
      (node (ref "SV11") (pin "13") (pinfunction "13_13") (pintype "passive"))
      (node (ref "SV12") (pin "13") (pinfunction "13_13") (pintype "passive"))
      (node (ref "SV13") (pin "13") (pinfunction "13_13") (pintype "passive"))
      (node (ref "SV14") (pin "13") (pinfunction "13_13") (pintype "passive"))
      (node (ref "SV15") (pin "13") (pinfunction "13_13") (pintype "passive"))
      (node (ref "SV16") (pin "13") (pinfunction "13_13") (pintype "passive"))
      (node (ref "SV17") (pin "13") (pinfunction "13_13") (pintype "passive"))
      (node (ref "SV18") (pin "13") (pinfunction "13_13") (pintype "passive"))
      (node (ref "SV2") (pin "26") (pinfunction "26_26") (pintype "passive"))
    )
    (net (code "27") (name "Net-(SV1-Pad27)") (class "Default")
      (node (ref "SV1") (pin "27") (pinfunction "27_27") (pintype "passive"))
      (node (ref "SV10") (pin "14") (pinfunction "14_14") (pintype "passive"))
      (node (ref "SV2") (pin "27") (pinfunction "27_27") (pintype "passive"))
      (node (ref "SV3") (pin "14") (pinfunction "14_14") (pintype "passive"))
      (node (ref "SV4") (pin "14") (pinfunction "14_14") (pintype "passive"))
      (node (ref "SV5") (pin "14") (pinfunction "14_14") (pintype "passive"))
      (node (ref "SV6") (pin "14") (pinfunction "14_14") (pintype "passive"))
      (node (ref "SV7") (pin "14") (pinfunction "14_14") (pintype "passive"))
      (node (ref "SV8") (pin "14") (pinfunction "14_14") (pintype "passive"))
      (node (ref "SV9") (pin "14") (pinfunction "14_14") (pintype "passive"))
    )
    (net (code "28") (name "Net-(SV1-Pad28)") (class "Default")
      (node (ref "SV1") (pin "28") (pinfunction "28_28") (pintype "passive"))
      (node (ref "SV11") (pin "14") (pinfunction "14_14") (pintype "passive"))
      (node (ref "SV12") (pin "14") (pinfunction "14_14") (pintype "passive"))
      (node (ref "SV13") (pin "14") (pinfunction "14_14") (pintype "passive"))
      (node (ref "SV14") (pin "14") (pinfunction "14_14") (pintype "passive"))
      (node (ref "SV15") (pin "14") (pinfunction "14_14") (pintype "passive"))
      (node (ref "SV16") (pin "14") (pinfunction "14_14") (pintype "passive"))
      (node (ref "SV17") (pin "14") (pinfunction "14_14") (pintype "passive"))
      (node (ref "SV18") (pin "14") (pinfunction "14_14") (pintype "passive"))
      (node (ref "SV2") (pin "28") (pinfunction "28_28") (pintype "passive"))
    )
    (net (code "29") (name "Net-(SV1-Pad29)") (class "Default")
      (node (ref "SV1") (pin "29") (pinfunction "29_29") (pintype "passive"))
      (node (ref "SV10") (pin "15") (pinfunction "15_15") (pintype "passive"))
      (node (ref "SV2") (pin "29") (pinfunction "29_29") (pintype "passive"))
      (node (ref "SV3") (pin "15") (pinfunction "15_15") (pintype "passive"))
      (node (ref "SV4") (pin "15") (pinfunction "15_15") (pintype "passive"))
      (node (ref "SV5") (pin "15") (pinfunction "15_15") (pintype "passive"))
      (node (ref "SV6") (pin "15") (pinfunction "15_15") (pintype "passive"))
      (node (ref "SV7") (pin "15") (pinfunction "15_15") (pintype "passive"))
      (node (ref "SV8") (pin "15") (pinfunction "15_15") (pintype "passive"))
      (node (ref "SV9") (pin "15") (pinfunction "15_15") (pintype "passive"))
    )
    (net (code "30") (name "Net-(SV1-Pad30)") (class "Default")
      (node (ref "SV1") (pin "30") (pinfunction "30_30") (pintype "passive"))
      (node (ref "SV11") (pin "15") (pinfunction "15_15") (pintype "passive"))
      (node (ref "SV12") (pin "15") (pinfunction "15_15") (pintype "passive"))
      (node (ref "SV13") (pin "15") (pinfunction "15_15") (pintype "passive"))
      (node (ref "SV14") (pin "15") (pinfunction "15_15") (pintype "passive"))
      (node (ref "SV15") (pin "15") (pinfunction "15_15") (pintype "passive"))
      (node (ref "SV16") (pin "15") (pinfunction "15_15") (pintype "passive"))
      (node (ref "SV17") (pin "15") (pinfunction "15_15") (pintype "passive"))
      (node (ref "SV18") (pin "15") (pinfunction "15_15") (pintype "passive"))
      (node (ref "SV2") (pin "30") (pinfunction "30_30") (pintype "passive"))
    )
    (net (code "31") (name "Net-(SV1-Pad31)") (class "Default")
      (node (ref "SV1") (pin "31") (pinfunction "31_31") (pintype "passive"))
      (node (ref "SV10") (pin "16") (pinfunction "16_16") (pintype "passive"))
      (node (ref "SV2") (pin "31") (pinfunction "31_31") (pintype "passive"))
      (node (ref "SV3") (pin "16") (pinfunction "16_16") (pintype "passive"))
      (node (ref "SV4") (pin "16") (pinfunction "16_16") (pintype "passive"))
      (node (ref "SV5") (pin "16") (pinfunction "16_16") (pintype "passive"))
      (node (ref "SV6") (pin "16") (pinfunction "16_16") (pintype "passive"))
      (node (ref "SV7") (pin "16") (pinfunction "16_16") (pintype "passive"))
      (node (ref "SV8") (pin "16") (pinfunction "16_16") (pintype "passive"))
      (node (ref "SV9") (pin "16") (pinfunction "16_16") (pintype "passive"))
    )
    (net (code "32") (name "Net-(SV1-Pad32)") (class "Default")
      (node (ref "SV1") (pin "32") (pinfunction "32_32") (pintype "passive"))
      (node (ref "SV11") (pin "16") (pinfunction "16_16") (pintype "passive"))
      (node (ref "SV12") (pin "16") (pinfunction "16_16") (pintype "passive"))
      (node (ref "SV13") (pin "16") (pinfunction "16_16") (pintype "passive"))
      (node (ref "SV14") (pin "16") (pinfunction "16_16") (pintype "passive"))
      (node (ref "SV15") (pin "16") (pinfunction "16_16") (pintype "passive"))
      (node (ref "SV16") (pin "16") (pinfunction "16_16") (pintype "passive"))
      (node (ref "SV17") (pin "16") (pinfunction "16_16") (pintype "passive"))
      (node (ref "SV18") (pin "16") (pinfunction "16_16") (pintype "passive"))
      (node (ref "SV2") (pin "32") (pinfunction "32_32") (pintype "passive"))
    )
    (net (code "33") (name "Net-(SV1-Pad33)") (class "Default")
      (node (ref "SV1") (pin "33") (pinfunction "33_33") (pintype "passive"))
      (node (ref "SV10") (pin "17") (pinfunction "17_17") (pintype "passive"))
      (node (ref "SV2") (pin "33") (pinfunction "33_33") (pintype "passive"))
      (node (ref "SV3") (pin "17") (pinfunction "17_17") (pintype "passive"))
      (node (ref "SV4") (pin "17") (pinfunction "17_17") (pintype "passive"))
      (node (ref "SV5") (pin "17") (pinfunction "17_17") (pintype "passive"))
      (node (ref "SV6") (pin "17") (pinfunction "17_17") (pintype "passive"))
      (node (ref "SV7") (pin "17") (pinfunction "17_17") (pintype "passive"))
      (node (ref "SV8") (pin "17") (pinfunction "17_17") (pintype "passive"))
      (node (ref "SV9") (pin "17") (pinfunction "17_17") (pintype "passive"))
    )
    (net (code "34") (name "Net-(SV1-Pad34)") (class "Default")
      (node (ref "SV1") (pin "34") (pinfunction "34_34") (pintype "passive"))
      (node (ref "SV11") (pin "17") (pinfunction "17_17") (pintype "passive"))
      (node (ref "SV12") (pin "17") (pinfunction "17_17") (pintype "passive"))
      (node (ref "SV13") (pin "17") (pinfunction "17_17") (pintype "passive"))
      (node (ref "SV14") (pin "17") (pinfunction "17_17") (pintype "passive"))
      (node (ref "SV15") (pin "17") (pinfunction "17_17") (pintype "passive"))
      (node (ref "SV16") (pin "17") (pinfunction "17_17") (pintype "passive"))
      (node (ref "SV17") (pin "17") (pinfunction "17_17") (pintype "passive"))
      (node (ref "SV18") (pin "17") (pinfunction "17_17") (pintype "passive"))
      (node (ref "SV2") (pin "34") (pinfunction "34_34") (pintype "passive"))
    )
    (net (code "35") (name "Net-(SV1-Pad35)") (class "Default")
      (node (ref "SV1") (pin "35") (pinfunction "35_35") (pintype "passive"))
      (node (ref "SV10") (pin "18") (pinfunction "18_18") (pintype "passive"))
      (node (ref "SV2") (pin "35") (pinfunction "35_35") (pintype "passive"))
      (node (ref "SV3") (pin "18") (pinfunction "18_18") (pintype "passive"))
      (node (ref "SV31") (pin "1") (pinfunction "1_1") (pintype "passive"))
      (node (ref "SV31") (pin "11") (pinfunction "11_11") (pintype "passive"))
      (node (ref "SV31") (pin "13") (pinfunction "13_13") (pintype "passive"))
      (node (ref "SV31") (pin "15") (pinfunction "15_15") (pintype "passive"))
      (node (ref "SV31") (pin "3") (pinfunction "3_3") (pintype "passive"))
      (node (ref "SV31") (pin "5") (pinfunction "5_5") (pintype "passive"))
      (node (ref "SV31") (pin "7") (pinfunction "7_7") (pintype "passive"))
      (node (ref "SV31") (pin "9") (pinfunction "9_9") (pintype "passive"))
      (node (ref "SV4") (pin "18") (pinfunction "18_18") (pintype "passive"))
      (node (ref "SV5") (pin "18") (pinfunction "18_18") (pintype "passive"))
      (node (ref "SV6") (pin "18") (pinfunction "18_18") (pintype "passive"))
      (node (ref "SV7") (pin "18") (pinfunction "18_18") (pintype "passive"))
      (node (ref "SV8") (pin "18") (pinfunction "18_18") (pintype "passive"))
      (node (ref "SV9") (pin "18") (pinfunction "18_18") (pintype "passive"))
    )
    (net (code "36") (name "Net-(SV1-Pad36)") (class "Default")
      (node (ref "SV1") (pin "36") (pinfunction "36_36") (pintype "passive"))
      (node (ref "SV11") (pin "18") (pinfunction "18_18") (pintype "passive"))
      (node (ref "SV12") (pin "18") (pinfunction "18_18") (pintype "passive"))
      (node (ref "SV13") (pin "18") (pinfunction "18_18") (pintype "passive"))
      (node (ref "SV14") (pin "18") (pinfunction "18_18") (pintype "passive"))
      (node (ref "SV15") (pin "18") (pinfunction "18_18") (pintype "passive"))
      (node (ref "SV16") (pin "18") (pinfunction "18_18") (pintype "passive"))
      (node (ref "SV17") (pin "18") (pinfunction "18_18") (pintype "passive"))
      (node (ref "SV18") (pin "18") (pinfunction "18_18") (pintype "passive"))
      (node (ref "SV2") (pin "36") (pinfunction "36_36") (pintype "passive"))
    )
    (net (code "37") (name "Net-(SV1-Pad37)") (class "Default")
      (node (ref "SV1") (pin "37") (pinfunction "37_37") (pintype "passive"))
      (node (ref "SV10") (pin "19") (pinfunction "19_19") (pintype "passive"))
      (node (ref "SV2") (pin "37") (pinfunction "37_37") (pintype "passive"))
      (node (ref "SV3") (pin "19") (pinfunction "19_19") (pintype "passive"))
      (node (ref "SV4") (pin "19") (pinfunction "19_19") (pintype "passive"))
      (node (ref "SV5") (pin "19") (pinfunction "19_19") (pintype "passive"))
      (node (ref "SV6") (pin "19") (pinfunction "19_19") (pintype "passive"))
      (node (ref "SV7") (pin "19") (pinfunction "19_19") (pintype "passive"))
      (node (ref "SV8") (pin "19") (pinfunction "19_19") (pintype "passive"))
      (node (ref "SV9") (pin "19") (pinfunction "19_19") (pintype "passive"))
    )
    (net (code "38") (name "Net-(SV1-Pad38)") (class "Default")
      (node (ref "SV1") (pin "38") (pinfunction "38_38") (pintype "passive"))
      (node (ref "SV11") (pin "19") (pinfunction "19_19") (pintype "passive"))
      (node (ref "SV12") (pin "19") (pinfunction "19_19") (pintype "passive"))
      (node (ref "SV13") (pin "19") (pinfunction "19_19") (pintype "passive"))
      (node (ref "SV14") (pin "19") (pinfunction "19_19") (pintype "passive"))
      (node (ref "SV15") (pin "19") (pinfunction "19_19") (pintype "passive"))
      (node (ref "SV16") (pin "19") (pinfunction "19_19") (pintype "passive"))
      (node (ref "SV17") (pin "19") (pinfunction "19_19") (pintype "passive"))
      (node (ref "SV18") (pin "19") (pinfunction "19_19") (pintype "passive"))
      (node (ref "SV2") (pin "38") (pinfunction "38_38") (pintype "passive"))
      (node (ref "SV32") (pin "1") (pinfunction "1_1") (pintype "passive"))
      (node (ref "SV32") (pin "11") (pinfunction "11_11") (pintype "passive"))
      (node (ref "SV32") (pin "13") (pinfunction "13_13") (pintype "passive"))
      (node (ref "SV32") (pin "15") (pinfunction "15_15") (pintype "passive"))
      (node (ref "SV32") (pin "3") (pinfunction "3_3") (pintype "passive"))
      (node (ref "SV32") (pin "5") (pinfunction "5_5") (pintype "passive"))
      (node (ref "SV32") (pin "7") (pinfunction "7_7") (pintype "passive"))
      (node (ref "SV32") (pin "9") (pinfunction "9_9") (pintype "passive"))
    )
    (net (code "39") (name "Net-(SV1-Pad39)") (class "Default")
      (node (ref "SV1") (pin "39") (pinfunction "39_39") (pintype "passive"))
      (node (ref "SV10") (pin "20") (pinfunction "20_20") (pintype "passive"))
      (node (ref "SV2") (pin "39") (pinfunction "39_39") (pintype "passive"))
      (node (ref "SV3") (pin "20") (pinfunction "20_20") (pintype "passive"))
      (node (ref "SV4") (pin "20") (pinfunction "20_20") (pintype "passive"))
      (node (ref "SV5") (pin "20") (pinfunction "20_20") (pintype "passive"))
      (node (ref "SV6") (pin "20") (pinfunction "20_20") (pintype "passive"))
      (node (ref "SV7") (pin "20") (pinfunction "20_20") (pintype "passive"))
      (node (ref "SV8") (pin "20") (pinfunction "20_20") (pintype "passive"))
      (node (ref "SV9") (pin "20") (pinfunction "20_20") (pintype "passive"))
    )
    (net (code "40") (name "Net-(SV1-Pad40)") (class "Default")
      (node (ref "SV1") (pin "40") (pinfunction "40_40") (pintype "passive"))
      (node (ref "SV11") (pin "20") (pinfunction "20_20") (pintype "passive"))
      (node (ref "SV12") (pin "20") (pinfunction "20_20") (pintype "passive"))
      (node (ref "SV13") (pin "20") (pinfunction "20_20") (pintype "passive"))
      (node (ref "SV14") (pin "20") (pinfunction "20_20") (pintype "passive"))
      (node (ref "SV15") (pin "20") (pinfunction "20_20") (pintype "passive"))
      (node (ref "SV16") (pin "20") (pinfunction "20_20") (pintype "passive"))
      (node (ref "SV17") (pin "20") (pinfunction "20_20") (pintype "passive"))
      (node (ref "SV18") (pin "20") (pinfunction "20_20") (pintype "passive"))
      (node (ref "SV2") (pin "40") (pinfunction "40_40") (pintype "passive"))
      (node (ref "SV31") (pin "10") (pinfunction "10_10") (pintype "passive"))
      (node (ref "SV31") (pin "12") (pinfunction "12_12") (pintype "passive"))
      (node (ref "SV31") (pin "14") (pinfunction "14_14") (pintype "passive"))
      (node (ref "SV31") (pin "16") (pinfunction "16_16") (pintype "passive"))
      (node (ref "SV31") (pin "2") (pinfunction "2_2") (pintype "passive"))
      (node (ref "SV31") (pin "4") (pinfunction "4_4") (pintype "passive"))
      (node (ref "SV31") (pin "6") (pinfunction "6_6") (pintype "passive"))
      (node (ref "SV31") (pin "8") (pinfunction "8_8") (pintype "passive"))
    )
    (net (code "41") (name "Net-(SV20-Pad1)") (class "Default")
      (node (ref "SV20") (pin "1") (pinfunction "1_1") (pintype "passive"))
      (node (ref "SV20") (pin "2") (pinfunction "2_2") (pintype "passive"))
      (node (ref "SV21") (pin "1") (pinfunction "1_1") (pintype "passive"))
      (node (ref "SV21") (pin "2") (pinfunction "2_2") (pintype "passive"))
    )
    (net (code "42") (name "Net-(SV20-Pad3)") (class "Default")
      (node (ref "SV20") (pin "3") (pinfunction "3_3") (pintype "passive"))
      (node (ref "SV20") (pin "4") (pinfunction "4_4") (pintype "passive"))
      (node (ref "SV21") (pin "3") (pinfunction "3_3") (pintype "passive"))
      (node (ref "SV21") (pin "4") (pinfunction "4_4") (pintype "passive"))
    )
    (net (code "43") (name "Net-(SV20-Pad5)") (class "Default")
      (node (ref "SV20") (pin "5") (pinfunction "5_5") (pintype "passive"))
      (node (ref "SV20") (pin "6") (pinfunction "6_6") (pintype "passive"))
      (node (ref "SV21") (pin "5") (pinfunction "5_5") (pintype "passive"))
      (node (ref "SV21") (pin "6") (pinfunction "6_6") (pintype "passive"))
    )
    (net (code "44") (name "Net-(SV20-Pad7)") (class "Default")
      (node (ref "SV20") (pin "7") (pinfunction "7_7") (pintype "passive"))
      (node (ref "SV20") (pin "8") (pinfunction "8_8") (pintype "passive"))
      (node (ref "SV21") (pin "7") (pinfunction "7_7") (pintype "passive"))
      (node (ref "SV21") (pin "8") (pinfunction "8_8") (pintype "passive"))
    )
    (net (code "45") (name "Net-(SV20-Pad10)") (class "Default")
      (node (ref "SV20") (pin "10") (pinfunction "10_10") (pintype "passive"))
      (node (ref "SV20") (pin "9") (pinfunction "9_9") (pintype "passive"))
      (node (ref "SV21") (pin "10") (pinfunction "10_10") (pintype "passive"))
      (node (ref "SV21") (pin "9") (pinfunction "9_9") (pintype "passive"))
    )
    (net (code "46") (name "Net-(SV20-Pad11)") (class "Default")
      (node (ref "SV20") (pin "11") (pinfunction "11_11") (pintype "passive"))
      (node (ref "SV20") (pin "12") (pinfunction "12_12") (pintype "passive"))
      (node (ref "SV21") (pin "11") (pinfunction "11_11") (pintype "passive"))
      (node (ref "SV21") (pin "12") (pinfunction "12_12") (pintype "passive"))
    )
    (net (code "47") (name "Net-(SV20-Pad13)") (class "Default")
      (node (ref "SV20") (pin "13") (pinfunction "13_13") (pintype "passive"))
      (node (ref "SV20") (pin "14") (pinfunction "14_14") (pintype "passive"))
      (node (ref "SV21") (pin "13") (pinfunction "13_13") (pintype "passive"))
      (node (ref "SV21") (pin "14") (pinfunction "14_14") (pintype "passive"))
    )
    (net (code "48") (name "Net-(SV20-Pad15)") (class "Default")
      (node (ref "SV20") (pin "15") (pinfunction "15_15") (pintype "passive"))
      (node (ref "SV20") (pin "16") (pinfunction "16_16") (pintype "passive"))
      (node (ref "SV21") (pin "15") (pinfunction "15_15") (pintype "passive"))
      (node (ref "SV21") (pin "16") (pinfunction "16_16") (pintype "passive"))
    )
    (net (code "49") (name "Net-(SV20-Pad17)") (class "Default")
      (node (ref "SV20") (pin "17") (pinfunction "17_17") (pintype "passive"))
      (node (ref "SV20") (pin "18") (pinfunction "18_18") (pintype "passive"))
      (node (ref "SV21") (pin "17") (pinfunction "17_17") (pintype "passive"))
      (node (ref "SV21") (pin "18") (pinfunction "18_18") (pintype "passive"))
    )
    (net (code "50") (name "Net-(SV20-Pad19)") (class "Default")
      (node (ref "SV20") (pin "19") (pinfunction "19_19") (pintype "passive"))
      (node (ref "SV20") (pin "20") (pinfunction "20_20") (pintype "passive"))
      (node (ref "SV21") (pin "19") (pinfunction "19_19") (pintype "passive"))
      (node (ref "SV21") (pin "20") (pinfunction "20_20") (pintype "passive"))
    )
    (net (code "51") (name "Net-(SV20-Pad21)") (class "Default")
      (node (ref "SV20") (pin "21") (pinfunction "21_21") (pintype "passive"))
      (node (ref "SV20") (pin "22") (pinfunction "22_22") (pintype "passive"))
      (node (ref "SV21") (pin "21") (pinfunction "21_21") (pintype "passive"))
      (node (ref "SV21") (pin "22") (pinfunction "22_22") (pintype "passive"))
    )
    (net (code "52") (name "Net-(SV20-Pad23)") (class "Default")
      (node (ref "SV20") (pin "23") (pinfunction "23_23") (pintype "passive"))
      (node (ref "SV20") (pin "24") (pinfunction "24_24") (pintype "passive"))
      (node (ref "SV21") (pin "23") (pinfunction "23_23") (pintype "passive"))
      (node (ref "SV21") (pin "24") (pinfunction "24_24") (pintype "passive"))
    )
    (net (code "53") (name "Net-(SV20-Pad25)") (class "Default")
      (node (ref "SV20") (pin "25") (pinfunction "25_25") (pintype "passive"))
      (node (ref "SV20") (pin "26") (pinfunction "26_26") (pintype "passive"))
      (node (ref "SV21") (pin "25") (pinfunction "25_25") (pintype "passive"))
      (node (ref "SV21") (pin "26") (pinfunction "26_26") (pintype "passive"))
    )
    (net (code "54") (name "Net-(SV20-Pad27)") (class "Default")
      (node (ref "SV20") (pin "27") (pinfunction "27_27") (pintype "passive"))
      (node (ref "SV20") (pin "28") (pinfunction "28_28") (pintype "passive"))
      (node (ref "SV21") (pin "27") (pinfunction "27_27") (pintype "passive"))
      (node (ref "SV21") (pin "28") (pinfunction "28_28") (pintype "passive"))
    )
    (net (code "55") (name "Net-(SV20-Pad29)") (class "Default")
      (node (ref "SV20") (pin "29") (pinfunction "29_29") (pintype "passive"))
      (node (ref "SV20") (pin "30") (pinfunction "30_30") (pintype "passive"))
      (node (ref "SV21") (pin "29") (pinfunction "29_29") (pintype "passive"))
      (node (ref "SV21") (pin "30") (pinfunction "30_30") (pintype "passive"))
    )
    (net (code "56") (name "Net-(SV20-Pad31)") (class "Default")
      (node (ref "SV20") (pin "31") (pinfunction "31_31") (pintype "passive"))
      (node (ref "SV20") (pin "32") (pinfunction "32_32") (pintype "passive"))
      (node (ref "SV21") (pin "31") (pinfunction "31_31") (pintype "passive"))
      (node (ref "SV21") (pin "32") (pinfunction "32_32") (pintype "passive"))
    )
    (net (code "57") (name "Net-(SV20-Pad33)") (class "Default")
      (node (ref "SV20") (pin "33") (pinfunction "33_33") (pintype "passive"))
      (node (ref "SV20") (pin "34") (pinfunction "34_34") (pintype "passive"))
      (node (ref "SV21") (pin "33") (pinfunction "33_33") (pintype "passive"))
      (node (ref "SV21") (pin "34") (pinfunction "34_34") (pintype "passive"))
    )
    (net (code "58") (name "Net-(SV20-Pad35)") (class "Default")
      (node (ref "SV20") (pin "35") (pinfunction "35_35") (pintype "passive"))
      (node (ref "SV20") (pin "36") (pinfunction "36_36") (pintype "passive"))
      (node (ref "SV21") (pin "35") (pinfunction "35_35") (pintype "passive"))
      (node (ref "SV21") (pin "36") (pinfunction "36_36") (pintype "passive"))
    )
    (net (code "59") (name "Net-(SV20-Pad37)") (class "Default")
      (node (ref "SV20") (pin "37") (pinfunction "37_37") (pintype "passive"))
      (node (ref "SV20") (pin "38") (pinfunction "38_38") (pintype "passive"))
      (node (ref "SV21") (pin "37") (pinfunction "37_37") (pintype "passive"))
      (node (ref "SV21") (pin "38") (pinfunction "38_38") (pintype "passive"))
    )
    (net (code "60") (name "Net-(SV20-Pad39)") (class "Default")
      (node (ref "SV20") (pin "39") (pinfunction "39_39") (pintype "passive"))
      (node (ref "SV20") (pin "40") (pinfunction "40_40") (pintype "passive"))
      (node (ref "SV21") (pin "39") (pinfunction "39_39") (pintype "passive"))
      (node (ref "SV21") (pin "40") (pinfunction "40_40") (pintype "passive"))
    )
    (net (code "61") (name "Net-(SV22-Pad1)") (class "Default")
      (node (ref "SV22") (pin "1") (pinfunction "1_1") (pintype "passive"))
      (node (ref "SV22") (pin "2") (pinfunction "2_2") (pintype "passive"))
      (node (ref "SV23") (pin "1") (pinfunction "1_1") (pintype "passive"))
      (node (ref "SV23") (pin "2") (pinfunction "2_2") (pintype "passive"))
    )
    (net (code "62") (name "Net-(SV22-Pad3)") (class "Default")
      (node (ref "SV22") (pin "3") (pinfunction "3_3") (pintype "passive"))
      (node (ref "SV22") (pin "4") (pinfunction "4_4") (pintype "passive"))
      (node (ref "SV23") (pin "3") (pinfunction "3_3") (pintype "passive"))
      (node (ref "SV23") (pin "4") (pinfunction "4_4") (pintype "passive"))
    )
    (net (code "63") (name "Net-(SV22-Pad5)") (class "Default")
      (node (ref "SV22") (pin "5") (pinfunction "5_5") (pintype "passive"))
      (node (ref "SV22") (pin "6") (pinfunction "6_6") (pintype "passive"))
      (node (ref "SV23") (pin "5") (pinfunction "5_5") (pintype "passive"))
      (node (ref "SV23") (pin "6") (pinfunction "6_6") (pintype "passive"))
    )
    (net (code "64") (name "Net-(SV22-Pad7)") (class "Default")
      (node (ref "SV22") (pin "7") (pinfunction "7_7") (pintype "passive"))
      (node (ref "SV22") (pin "8") (pinfunction "8_8") (pintype "passive"))
      (node (ref "SV23") (pin "7") (pinfunction "7_7") (pintype "passive"))
      (node (ref "SV23") (pin "8") (pinfunction "8_8") (pintype "passive"))
    )
    (net (code "65") (name "Net-(SV22-Pad10)") (class "Default")
      (node (ref "SV22") (pin "10") (pinfunction "10_10") (pintype "passive"))
      (node (ref "SV22") (pin "9") (pinfunction "9_9") (pintype "passive"))
      (node (ref "SV23") (pin "10") (pinfunction "10_10") (pintype "passive"))
      (node (ref "SV23") (pin "9") (pinfunction "9_9") (pintype "passive"))
    )
    (net (code "66") (name "Net-(SV22-Pad11)") (class "Default")
      (node (ref "SV22") (pin "11") (pinfunction "11_11") (pintype "passive"))
      (node (ref "SV22") (pin "12") (pinfunction "12_12") (pintype "passive"))
      (node (ref "SV23") (pin "11") (pinfunction "11_11") (pintype "passive"))
      (node (ref "SV23") (pin "12") (pinfunction "12_12") (pintype "passive"))
    )
    (net (code "67") (name "Net-(SV22-Pad13)") (class "Default")
      (node (ref "SV22") (pin "13") (pinfunction "13_13") (pintype "passive"))
      (node (ref "SV22") (pin "14") (pinfunction "14_14") (pintype "passive"))
      (node (ref "SV23") (pin "13") (pinfunction "13_13") (pintype "passive"))
      (node (ref "SV23") (pin "14") (pinfunction "14_14") (pintype "passive"))
    )
    (net (code "68") (name "Net-(SV22-Pad15)") (class "Default")
      (node (ref "SV22") (pin "15") (pinfunction "15_15") (pintype "passive"))
      (node (ref "SV22") (pin "16") (pinfunction "16_16") (pintype "passive"))
      (node (ref "SV23") (pin "15") (pinfunction "15_15") (pintype "passive"))
      (node (ref "SV23") (pin "16") (pinfunction "16_16") (pintype "passive"))
    )
    (net (code "69") (name "Net-(SV22-Pad17)") (class "Default")
      (node (ref "SV22") (pin "17") (pinfunction "17_17") (pintype "passive"))
      (node (ref "SV22") (pin "18") (pinfunction "18_18") (pintype "passive"))
      (node (ref "SV23") (pin "17") (pinfunction "17_17") (pintype "passive"))
      (node (ref "SV23") (pin "18") (pinfunction "18_18") (pintype "passive"))
    )
    (net (code "70") (name "Net-(SV22-Pad19)") (class "Default")
      (node (ref "SV22") (pin "19") (pinfunction "19_19") (pintype "passive"))
      (node (ref "SV22") (pin "20") (pinfunction "20_20") (pintype "passive"))
      (node (ref "SV23") (pin "19") (pinfunction "19_19") (pintype "passive"))
      (node (ref "SV23") (pin "20") (pinfunction "20_20") (pintype "passive"))
    )
    (net (code "71") (name "Net-(SV22-Pad21)") (class "Default")
      (node (ref "SV22") (pin "21") (pinfunction "21_21") (pintype "passive"))
      (node (ref "SV22") (pin "22") (pinfunction "22_22") (pintype "passive"))
      (node (ref "SV23") (pin "21") (pinfunction "21_21") (pintype "passive"))
      (node (ref "SV23") (pin "22") (pinfunction "22_22") (pintype "passive"))
    )
    (net (code "72") (name "Net-(SV22-Pad23)") (class "Default")
      (node (ref "SV22") (pin "23") (pinfunction "23_23") (pintype "passive"))
      (node (ref "SV22") (pin "24") (pinfunction "24_24") (pintype "passive"))
      (node (ref "SV23") (pin "23") (pinfunction "23_23") (pintype "passive"))
      (node (ref "SV23") (pin "24") (pinfunction "24_24") (pintype "passive"))
    )
    (net (code "73") (name "Net-(SV22-Pad25)") (class "Default")
      (node (ref "SV22") (pin "25") (pinfunction "25_25") (pintype "passive"))
      (node (ref "SV22") (pin "26") (pinfunction "26_26") (pintype "passive"))
      (node (ref "SV23") (pin "25") (pinfunction "25_25") (pintype "passive"))
      (node (ref "SV23") (pin "26") (pinfunction "26_26") (pintype "passive"))
    )
    (net (code "74") (name "Net-(SV22-Pad27)") (class "Default")
      (node (ref "SV22") (pin "27") (pinfunction "27_27") (pintype "passive"))
      (node (ref "SV22") (pin "28") (pinfunction "28_28") (pintype "passive"))
      (node (ref "SV23") (pin "27") (pinfunction "27_27") (pintype "passive"))
      (node (ref "SV23") (pin "28") (pinfunction "28_28") (pintype "passive"))
    )
    (net (code "75") (name "Net-(SV22-Pad29)") (class "Default")
      (node (ref "SV22") (pin "29") (pinfunction "29_29") (pintype "passive"))
      (node (ref "SV22") (pin "30") (pinfunction "30_30") (pintype "passive"))
      (node (ref "SV23") (pin "29") (pinfunction "29_29") (pintype "passive"))
      (node (ref "SV23") (pin "30") (pinfunction "30_30") (pintype "passive"))
    )
    (net (code "76") (name "Net-(SV22-Pad31)") (class "Default")
      (node (ref "SV22") (pin "31") (pinfunction "31_31") (pintype "passive"))
      (node (ref "SV22") (pin "32") (pinfunction "32_32") (pintype "passive"))
      (node (ref "SV23") (pin "31") (pinfunction "31_31") (pintype "passive"))
      (node (ref "SV23") (pin "32") (pinfunction "32_32") (pintype "passive"))
    )
    (net (code "77") (name "Net-(SV22-Pad33)") (class "Default")
      (node (ref "SV22") (pin "33") (pinfunction "33_33") (pintype "passive"))
      (node (ref "SV22") (pin "34") (pinfunction "34_34") (pintype "passive"))
      (node (ref "SV23") (pin "33") (pinfunction "33_33") (pintype "passive"))
      (node (ref "SV23") (pin "34") (pinfunction "34_34") (pintype "passive"))
    )
    (net (code "78") (name "Net-(SV22-Pad35)") (class "Default")
      (node (ref "SV22") (pin "35") (pinfunction "35_35") (pintype "passive"))
      (node (ref "SV22") (pin "36") (pinfunction "36_36") (pintype "passive"))
      (node (ref "SV23") (pin "35") (pinfunction "35_35") (pintype "passive"))
      (node (ref "SV23") (pin "36") (pinfunction "36_36") (pintype "passive"))
    )
    (net (code "79") (name "Net-(SV22-Pad37)") (class "Default")
      (node (ref "SV22") (pin "37") (pinfunction "37_37") (pintype "passive"))
      (node (ref "SV22") (pin "38") (pinfunction "38_38") (pintype "passive"))
      (node (ref "SV23") (pin "37") (pinfunction "37_37") (pintype "passive"))
      (node (ref "SV23") (pin "38") (pinfunction "38_38") (pintype "passive"))
    )
    (net (code "80") (name "Net-(SV22-Pad39)") (class "Default")
      (node (ref "SV22") (pin "39") (pinfunction "39_39") (pintype "passive"))
      (node (ref "SV22") (pin "40") (pinfunction "40_40") (pintype "passive"))
      (node (ref "SV23") (pin "39") (pinfunction "39_39") (pintype "passive"))
      (node (ref "SV23") (pin "40") (pinfunction "40_40") (pintype "passive"))
    )
    (net (code "81") (name "Net-(SV24-Pad1)") (class "Default")
      (node (ref "SV24") (pin "1") (pinfunction "1_1") (pintype "passive"))
      (node (ref "SV24") (pin "2") (pinfunction "2_2") (pintype "passive"))
      (node (ref "SV25") (pin "1") (pinfunction "1_1") (pintype "passive"))
      (node (ref "SV25") (pin "2") (pinfunction "2_2") (pintype "passive"))
    )
    (net (code "82") (name "Net-(SV24-Pad3)") (class "Default")
      (node (ref "SV24") (pin "3") (pinfunction "3_3") (pintype "passive"))
      (node (ref "SV24") (pin "4") (pinfunction "4_4") (pintype "passive"))
      (node (ref "SV25") (pin "3") (pinfunction "3_3") (pintype "passive"))
      (node (ref "SV25") (pin "4") (pinfunction "4_4") (pintype "passive"))
    )
    (net (code "83") (name "Net-(SV24-Pad5)") (class "Default")
      (node (ref "SV24") (pin "5") (pinfunction "5_5") (pintype "passive"))
      (node (ref "SV24") (pin "6") (pinfunction "6_6") (pintype "passive"))
      (node (ref "SV25") (pin "5") (pinfunction "5_5") (pintype "passive"))
      (node (ref "SV25") (pin "6") (pinfunction "6_6") (pintype "passive"))
    )
    (net (code "84") (name "Net-(SV24-Pad7)") (class "Default")
      (node (ref "SV24") (pin "7") (pinfunction "7_7") (pintype "passive"))
      (node (ref "SV24") (pin "8") (pinfunction "8_8") (pintype "passive"))
      (node (ref "SV25") (pin "7") (pinfunction "7_7") (pintype "passive"))
      (node (ref "SV25") (pin "8") (pinfunction "8_8") (pintype "passive"))
    )
    (net (code "85") (name "Net-(SV24-Pad10)") (class "Default")
      (node (ref "SV24") (pin "10") (pinfunction "10_10") (pintype "passive"))
      (node (ref "SV24") (pin "9") (pinfunction "9_9") (pintype "passive"))
      (node (ref "SV25") (pin "10") (pinfunction "10_10") (pintype "passive"))
      (node (ref "SV25") (pin "9") (pinfunction "9_9") (pintype "passive"))
    )
    (net (code "86") (name "Net-(SV24-Pad11)") (class "Default")
      (node (ref "SV24") (pin "11") (pinfunction "11_11") (pintype "passive"))
      (node (ref "SV24") (pin "12") (pinfunction "12_12") (pintype "passive"))
      (node (ref "SV25") (pin "11") (pinfunction "11_11") (pintype "passive"))
      (node (ref "SV25") (pin "12") (pinfunction "12_12") (pintype "passive"))
    )
    (net (code "87") (name "Net-(SV24-Pad13)") (class "Default")
      (node (ref "SV24") (pin "13") (pinfunction "13_13") (pintype "passive"))
      (node (ref "SV24") (pin "14") (pinfunction "14_14") (pintype "passive"))
      (node (ref "SV25") (pin "13") (pinfunction "13_13") (pintype "passive"))
      (node (ref "SV25") (pin "14") (pinfunction "14_14") (pintype "passive"))
    )
    (net (code "88") (name "Net-(SV24-Pad15)") (class "Default")
      (node (ref "SV24") (pin "15") (pinfunction "15_15") (pintype "passive"))
      (node (ref "SV24") (pin "16") (pinfunction "16_16") (pintype "passive"))
      (node (ref "SV25") (pin "15") (pinfunction "15_15") (pintype "passive"))
      (node (ref "SV25") (pin "16") (pinfunction "16_16") (pintype "passive"))
    )
    (net (code "89") (name "Net-(SV24-Pad17)") (class "Default")
      (node (ref "SV24") (pin "17") (pinfunction "17_17") (pintype "passive"))
      (node (ref "SV24") (pin "18") (pinfunction "18_18") (pintype "passive"))
      (node (ref "SV25") (pin "17") (pinfunction "17_17") (pintype "passive"))
      (node (ref "SV25") (pin "18") (pinfunction "18_18") (pintype "passive"))
    )
    (net (code "90") (name "Net-(SV24-Pad19)") (class "Default")
      (node (ref "SV24") (pin "19") (pinfunction "19_19") (pintype "passive"))
      (node (ref "SV24") (pin "20") (pinfunction "20_20") (pintype "passive"))
      (node (ref "SV25") (pin "19") (pinfunction "19_19") (pintype "passive"))
      (node (ref "SV25") (pin "20") (pinfunction "20_20") (pintype "passive"))
    )
    (net (code "91") (name "Net-(SV24-Pad21)") (class "Default")
      (node (ref "SV24") (pin "21") (pinfunction "21_21") (pintype "passive"))
      (node (ref "SV24") (pin "22") (pinfunction "22_22") (pintype "passive"))
      (node (ref "SV25") (pin "21") (pinfunction "21_21") (pintype "passive"))
      (node (ref "SV25") (pin "22") (pinfunction "22_22") (pintype "passive"))
    )
    (net (code "92") (name "Net-(SV24-Pad23)") (class "Default")
      (node (ref "SV24") (pin "23") (pinfunction "23_23") (pintype "passive"))
      (node (ref "SV24") (pin "24") (pinfunction "24_24") (pintype "passive"))
      (node (ref "SV25") (pin "23") (pinfunction "23_23") (pintype "passive"))
      (node (ref "SV25") (pin "24") (pinfunction "24_24") (pintype "passive"))
    )
    (net (code "93") (name "Net-(SV24-Pad25)") (class "Default")
      (node (ref "SV24") (pin "25") (pinfunction "25_25") (pintype "passive"))
      (node (ref "SV24") (pin "26") (pinfunction "26_26") (pintype "passive"))
      (node (ref "SV25") (pin "25") (pinfunction "25_25") (pintype "passive"))
      (node (ref "SV25") (pin "26") (pinfunction "26_26") (pintype "passive"))
    )
    (net (code "94") (name "Net-(SV24-Pad27)") (class "Default")
      (node (ref "SV24") (pin "27") (pinfunction "27_27") (pintype "passive"))
      (node (ref "SV24") (pin "28") (pinfunction "28_28") (pintype "passive"))
      (node (ref "SV25") (pin "27") (pinfunction "27_27") (pintype "passive"))
      (node (ref "SV25") (pin "28") (pinfunction "28_28") (pintype "passive"))
    )
    (net (code "95") (name "Net-(SV24-Pad29)") (class "Default")
      (node (ref "SV24") (pin "29") (pinfunction "29_29") (pintype "passive"))
      (node (ref "SV24") (pin "30") (pinfunction "30_30") (pintype "passive"))
      (node (ref "SV25") (pin "29") (pinfunction "29_29") (pintype "passive"))
      (node (ref "SV25") (pin "30") (pinfunction "30_30") (pintype "passive"))
    )
    (net (code "96") (name "Net-(SV24-Pad31)") (class "Default")
      (node (ref "SV24") (pin "31") (pinfunction "31_31") (pintype "passive"))
      (node (ref "SV24") (pin "32") (pinfunction "32_32") (pintype "passive"))
      (node (ref "SV25") (pin "31") (pinfunction "31_31") (pintype "passive"))
      (node (ref "SV25") (pin "32") (pinfunction "32_32") (pintype "passive"))
    )
    (net (code "97") (name "Net-(SV24-Pad33)") (class "Default")
      (node (ref "SV24") (pin "33") (pinfunction "33_33") (pintype "passive"))
      (node (ref "SV24") (pin "34") (pinfunction "34_34") (pintype "passive"))
      (node (ref "SV25") (pin "33") (pinfunction "33_33") (pintype "passive"))
      (node (ref "SV25") (pin "34") (pinfunction "34_34") (pintype "passive"))
    )
    (net (code "98") (name "Net-(SV24-Pad35)") (class "Default")
      (node (ref "SV24") (pin "35") (pinfunction "35_35") (pintype "passive"))
      (node (ref "SV24") (pin "36") (pinfunction "36_36") (pintype "passive"))
      (node (ref "SV25") (pin "35") (pinfunction "35_35") (pintype "passive"))
      (node (ref "SV25") (pin "36") (pinfunction "36_36") (pintype "passive"))
    )
    (net (code "99") (name "Net-(SV24-Pad37)") (class "Default")
      (node (ref "SV24") (pin "37") (pinfunction "37_37") (pintype "passive"))
      (node (ref "SV24") (pin "38") (pinfunction "38_38") (pintype "passive"))
      (node (ref "SV25") (pin "37") (pinfunction "37_37") (pintype "passive"))
      (node (ref "SV25") (pin "38") (pinfunction "38_38") (pintype "passive"))
    )
    (net (code "100") (name "Net-(SV24-Pad39)") (class "Default")
      (node (ref "SV24") (pin "39") (pinfunction "39_39") (pintype "passive"))
      (node (ref "SV24") (pin "40") (pinfunction "40_40") (pintype "passive"))
      (node (ref "SV25") (pin "39") (pinfunction "39_39") (pintype "passive"))
      (node (ref "SV25") (pin "40") (pinfunction "40_40") (pintype "passive"))
    )
  )
)
